# legatus_1_3.net
KiCad netlist of a schematic drawn in EAGLE
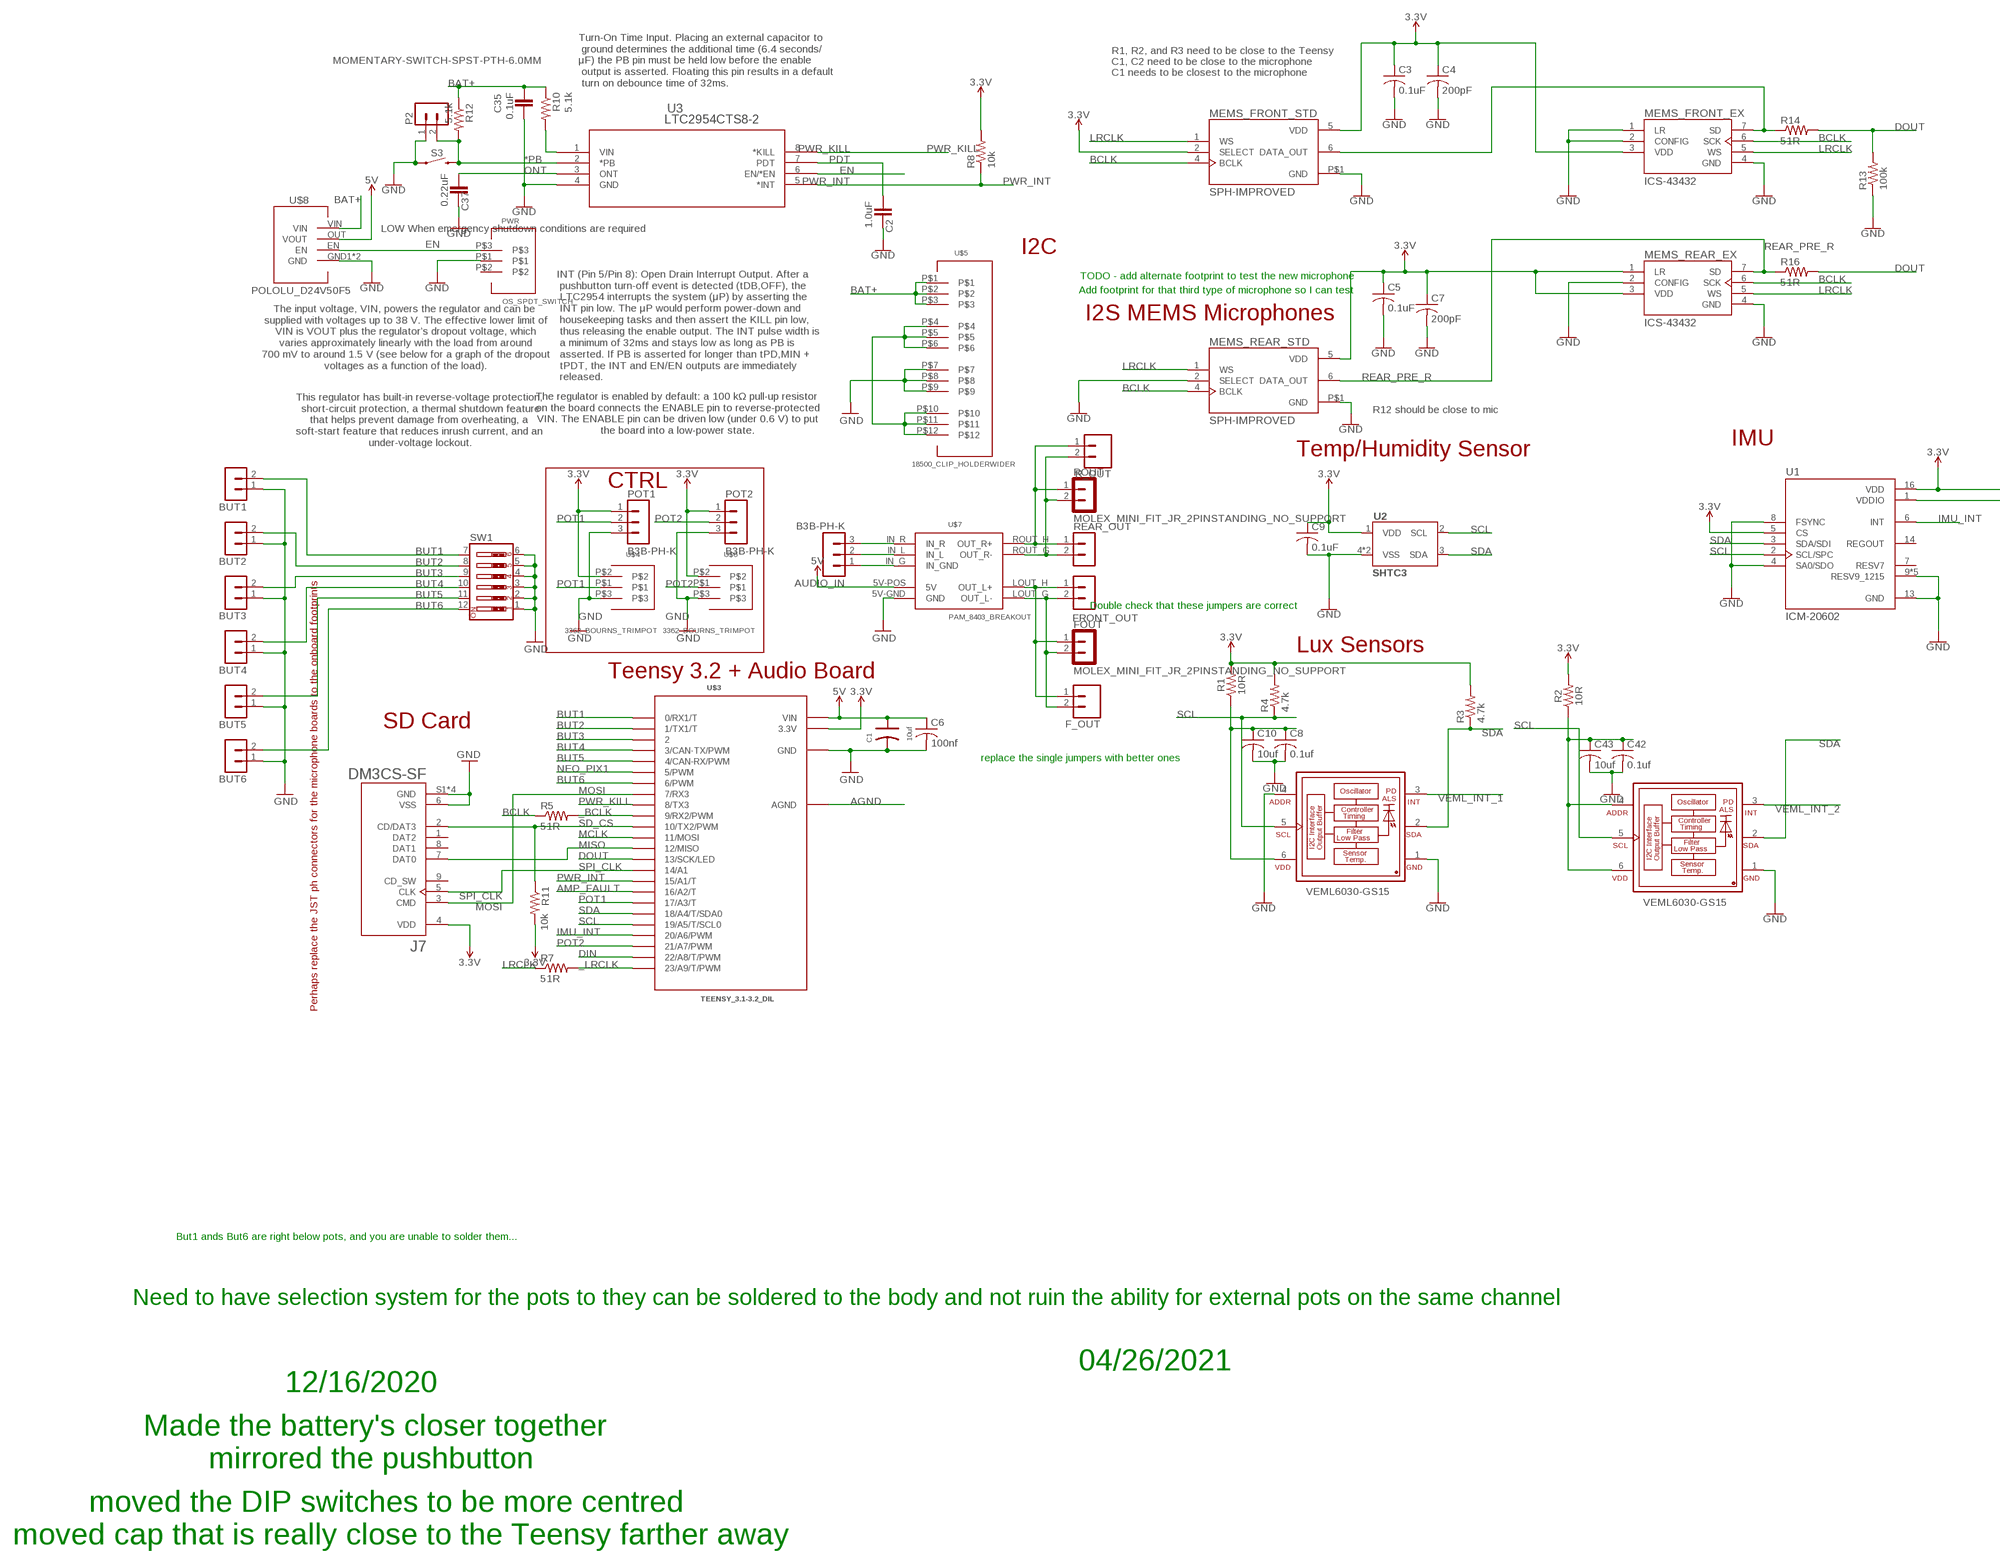
[diagram p0: schematic, sheet 1, part 1 of 2]
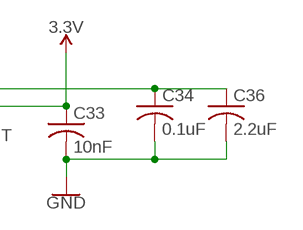
[diagram p1: schematic, sheet 1, part 2 of 2]
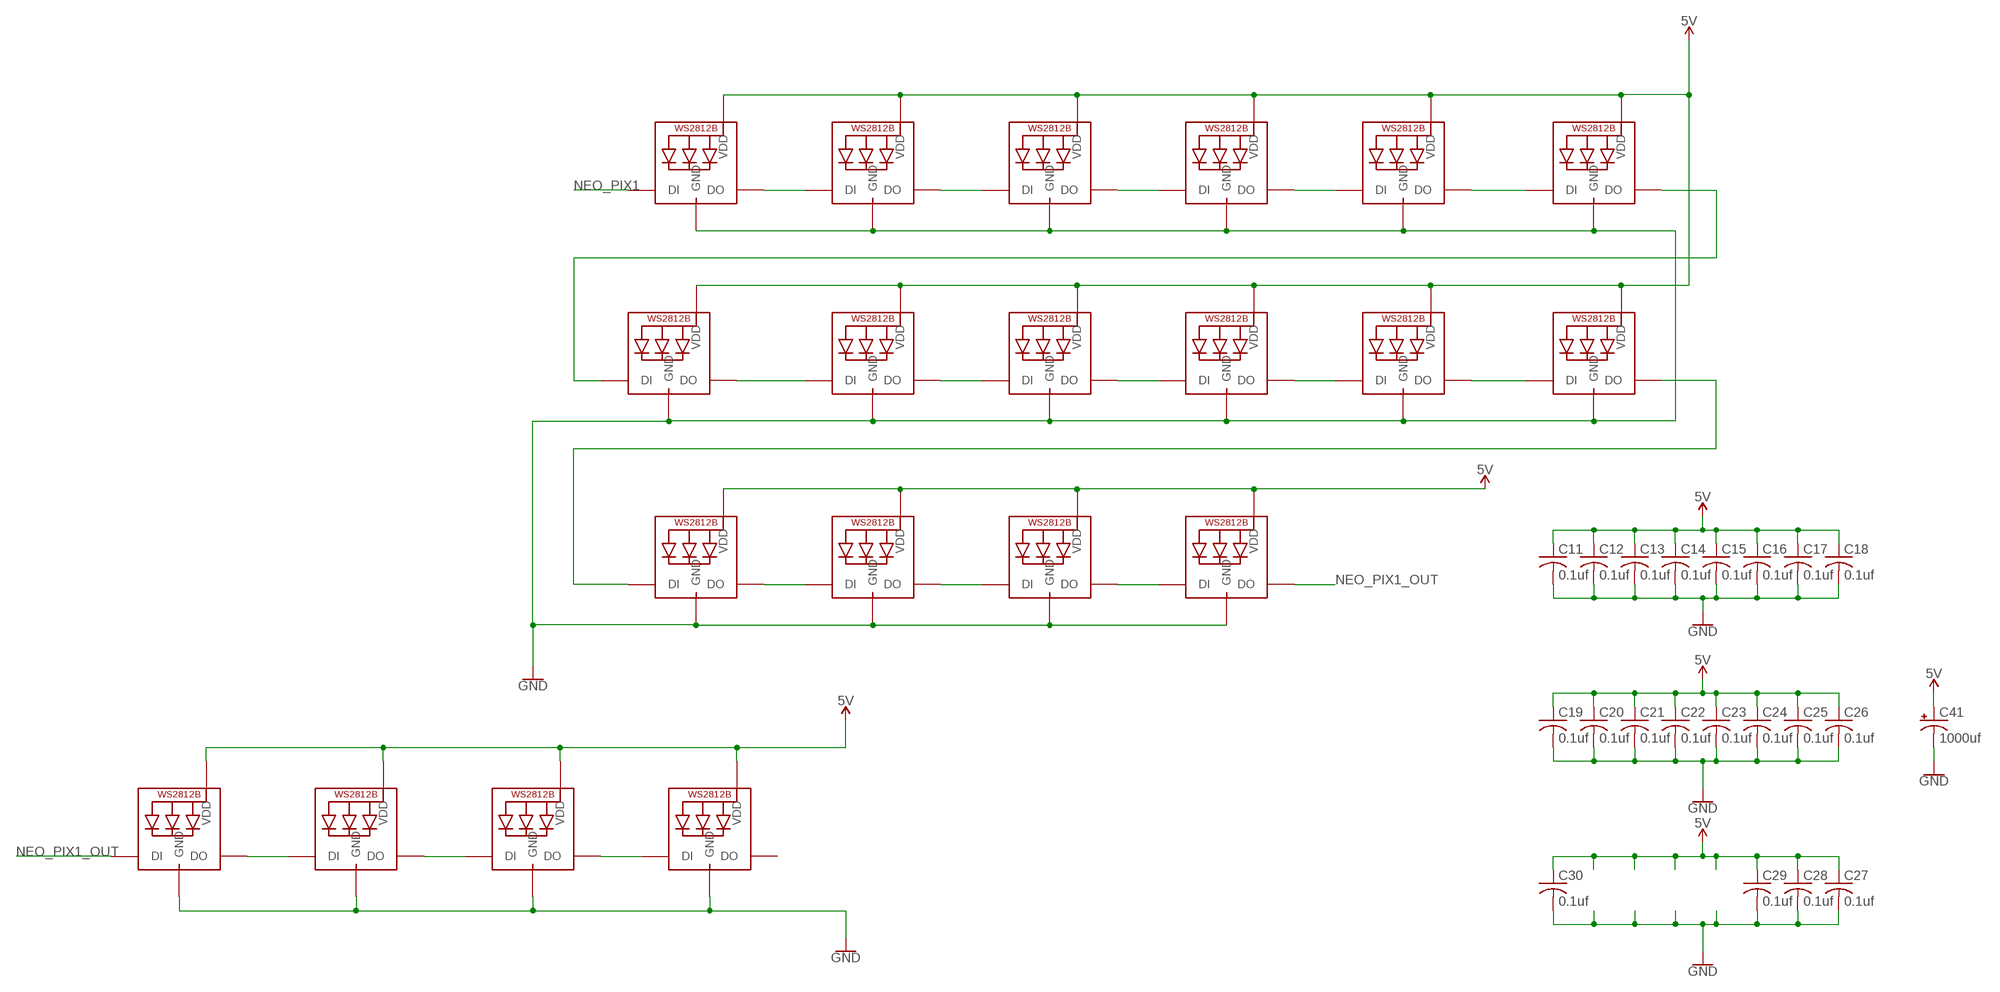
[diagram p2: schematic, sheet 2]

(export (version "E")
  (design (tool "Eeschema 10.0.6"))
  (components
    (comp (ref "C11")
      (value "0.1uf")
      (footprint "eagle-import:C0805")
      (libsource (lib "eagle-import") (part "rcl_334_C-USC0805"))
    )
    (comp (ref "C12")
      (value "0.1uf")
      (footprint "eagle-import:C0805")
      (libsource (lib "eagle-import") (part "rcl_334_C-USC0805"))
    )
    (comp (ref "C13")
      (value "0.1uf")
      (footprint "eagle-import:C0805")
      (libsource (lib "eagle-import") (part "rcl_334_C-USC0805"))
    )
    (comp (ref "C14")
      (value "0.1uf")
      (footprint "eagle-import:C0805")
      (libsource (lib "eagle-import") (part "rcl_334_C-USC0805"))
    )
    (comp (ref "C15")
      (value "0.1uf")
      (footprint "eagle-import:C0805")
      (libsource (lib "eagle-import") (part "rcl_334_C-USC0805"))
    )
    (comp (ref "C16")
      (value "0.1uf")
      (footprint "eagle-import:C0805")
      (libsource (lib "eagle-import") (part "rcl_334_C-USC0805"))
    )
    (comp (ref "C17")
      (value "0.1uf")
      (footprint "eagle-import:C0805")
      (libsource (lib "eagle-import") (part "rcl_334_C-USC0805"))
    )
    (comp (ref "C18")
      (value "0.1uf")
      (footprint "eagle-import:C0805")
      (libsource (lib "eagle-import") (part "rcl_334_C-USC0805"))
    )
    (comp (ref "C19")
      (value "0.1uf")
      (footprint "eagle-import:C0805")
      (libsource (lib "eagle-import") (part "rcl_334_C-USC0805"))
    )
    (comp (ref "C20")
      (value "0.1uf")
      (footprint "eagle-import:C0805")
      (libsource (lib "eagle-import") (part "rcl_334_C-USC0805"))
    )
    (comp (ref "C21")
      (value "0.1uf")
      (footprint "eagle-import:C0805")
      (libsource (lib "eagle-import") (part "rcl_334_C-USC0805"))
    )
    (comp (ref "C22")
      (value "0.1uf")
      (footprint "eagle-import:C0805")
      (libsource (lib "eagle-import") (part "rcl_334_C-USC0805"))
    )
    (comp (ref "C23")
      (value "0.1uf")
      (footprint "eagle-import:C0805")
      (libsource (lib "eagle-import") (part "rcl_334_C-USC0805"))
    )
    (comp (ref "C24")
      (value "0.1uf")
      (footprint "eagle-import:C0805")
      (libsource (lib "eagle-import") (part "rcl_334_C-USC0805"))
    )
    (comp (ref "C25")
      (value "0.1uf")
      (footprint "eagle-import:C0805")
      (libsource (lib "eagle-import") (part "rcl_334_C-USC0805"))
    )
    (comp (ref "C26")
      (value "0.1uf")
      (footprint "eagle-import:C0805")
      (libsource (lib "eagle-import") (part "rcl_334_C-USC0805"))
    )
    (comp (ref "C27")
      (value "0.1uf")
      (footprint "eagle-import:C0805")
      (libsource (lib "eagle-import") (part "rcl_334_C-USC0805"))
    )
    (comp (ref "C28")
      (value "0.1uf")
      (footprint "eagle-import:C0805")
      (libsource (lib "eagle-import") (part "rcl_334_C-USC0805"))
    )
    (comp (ref "C29")
      (value "0.1uf")
      (footprint "eagle-import:C0805")
      (libsource (lib "eagle-import") (part "rcl_334_C-USC0805"))
    )
    (comp (ref "C30")
      (value "0.1uf")
      (footprint "eagle-import:C0805")
      (libsource (lib "eagle-import") (part "rcl_334_C-USC0805"))
    )
    (comp (ref "C41")
      (value "1000uf")
      (footprint "eagle-import:153CLV-1010")
      (libsource (lib "eagle-import") (part "CPOL-US153CLV-1010"))
    )
    (comp (ref "LED1")
      (value "WS2812B_5050N")
      (footprint "eagle-import:WS2812B-NARROW")
      (libsource (lib "eagle-import") (part "WS2812B_5050N"))
    )
    (comp (ref "LED2")
      (value "WS2812B_5050N")
      (footprint "eagle-import:WS2812B-NARROW")
      (libsource (lib "eagle-import") (part "WS2812B_5050N"))
    )
    (comp (ref "LED3")
      (value "WS2812B_5050N")
      (footprint "eagle-import:WS2812B-NARROW")
      (libsource (lib "eagle-import") (part "WS2812B_5050N"))
    )
    (comp (ref "LED4")
      (value "WS2812B_5050N")
      (footprint "eagle-import:WS2812B-NARROW")
      (libsource (lib "eagle-import") (part "WS2812B_5050N"))
    )
    (comp (ref "LED5")
      (value "WS2812B_5050N")
      (footprint "eagle-import:WS2812B-NARROW")
      (libsource (lib "eagle-import") (part "WS2812B_5050N"))
    )
    (comp (ref "LED6")
      (value "WS2812B_5050N")
      (footprint "eagle-import:WS2812B-NARROW")
      (libsource (lib "eagle-import") (part "WS2812B_5050N"))
    )
    (comp (ref "LED7")
      (value "WS2812B_5050N")
      (footprint "eagle-import:WS2812B-NARROW")
      (libsource (lib "eagle-import") (part "WS2812B_5050N"))
    )
    (comp (ref "LED8")
      (value "WS2812B_5050N")
      (footprint "eagle-import:WS2812B-NARROW")
      (libsource (lib "eagle-import") (part "WS2812B_5050N"))
    )
    (comp (ref "LED9")
      (value "WS2812B_5050N")
      (footprint "eagle-import:WS2812B-NARROW")
      (libsource (lib "eagle-import") (part "WS2812B_5050N"))
    )
    (comp (ref "LED10")
      (value "WS2812B_5050N")
      (footprint "eagle-import:WS2812B-NARROW")
      (libsource (lib "eagle-import") (part "WS2812B_5050N"))
    )
    (comp (ref "LED11")
      (value "WS2812B_5050N")
      (footprint "eagle-import:WS2812B-NARROW")
      (libsource (lib "eagle-import") (part "WS2812B_5050N"))
    )
    (comp (ref "LED12")
      (value "WS2812B_5050N")
      (footprint "eagle-import:WS2812B-NARROW")
      (libsource (lib "eagle-import") (part "WS2812B_5050N"))
    )
    (comp (ref "LED13")
      (value "WS2812B_5050N")
      (footprint "eagle-import:WS2812B-NARROW")
      (libsource (lib "eagle-import") (part "WS2812B_5050N"))
    )
    (comp (ref "LED14")
      (value "WS2812B_5050N")
      (footprint "eagle-import:WS2812B-NARROW")
      (libsource (lib "eagle-import") (part "WS2812B_5050N"))
    )
    (comp (ref "LED15")
      (value "WS2812B_5050N")
      (footprint "eagle-import:WS2812B-NARROW")
      (libsource (lib "eagle-import") (part "WS2812B_5050N"))
    )
    (comp (ref "LED16")
      (value "WS2812B_5050N")
      (footprint "eagle-import:WS2812B-NARROW")
      (libsource (lib "eagle-import") (part "WS2812B_5050N"))
    )
    (comp (ref "LED17")
      (value "WS2812B_5050N")
      (footprint "eagle-import:WS2812B-NARROW")
      (libsource (lib "eagle-import") (part "WS2812B_5050N"))
    )
    (comp (ref "LED18")
      (value "WS2812B_5050N")
      (footprint "eagle-import:WS2812B-NARROW")
      (libsource (lib "eagle-import") (part "WS2812B_5050N"))
    )
    (comp (ref "LED19")
      (value "WS2812B_5050N")
      (footprint "eagle-import:WS2812B-NARROW")
      (libsource (lib "eagle-import") (part "WS2812B_5050N"))
    )
    (comp (ref "LED20")
      (value "WS2812B_5050N")
      (footprint "eagle-import:WS2812B-NARROW")
      (libsource (lib "eagle-import") (part "WS2812B_5050N"))
    )
    (comp (ref "AUDIO_IN")
      (value "B3B-PH-K")
      (footprint "eagle-import:B3B-PH-K")
      (libsource (lib "eagle-import") (part "B3B-PH-K"))
    )
    (comp (ref "BUT1")
      (value "B2B-PH-K")
      (footprint "eagle-import:B2B-PH-K")
      (libsource (lib "eagle-import") (part "B2B-PH-K"))
    )
    (comp (ref "BUT2")
      (value "B2B-PH-K")
      (footprint "eagle-import:B2B-PH-K")
      (libsource (lib "eagle-import") (part "B2B-PH-K"))
    )
    (comp (ref "BUT3")
      (value "B2B-PH-K")
      (footprint "eagle-import:B2B-PH-K")
      (libsource (lib "eagle-import") (part "B2B-PH-K"))
    )
    (comp (ref "BUT4")
      (value "B2B-PH-K")
      (footprint "eagle-import:B2B-PH-K")
      (libsource (lib "eagle-import") (part "B2B-PH-K"))
    )
    (comp (ref "BUT5")
      (value "B2B-PH-K")
      (footprint "eagle-import:B2B-PH-K")
      (libsource (lib "eagle-import") (part "B2B-PH-K"))
    )
    (comp (ref "BUT6")
      (value "B2B-PH-K")
      (footprint "eagle-import:B2B-PH-K")
      (libsource (lib "eagle-import") (part "B2B-PH-K"))
    )
    (comp (ref "C1")
      (value "10uf")
      (footprint "eagle-import:PC-D5.3MM")
      (fields (field (name "MPN") "KS 100uF/16V"))
      (libsource (lib "eagle-import") (part "DIP-ALUMINUM-47UF-16V(D5-H7MM)"))
    )
    (comp (ref "C2")
      (value "1.0uF")
      (footprint "eagle-import:CAPC2012X110")
      (libsource (lib "eagle-import") (part "CCHIP-0805(2012-METRIC)_"))
    )
    (comp (ref "C3")
      (value "0.1uF")
      (footprint "eagle-import:C0805")
      (libsource (lib "eagle-import") (part "rcl_334_C-USC0805"))
    )
    (comp (ref "C4")
      (value "200pF")
      (footprint "eagle-import:C0805")
      (libsource (lib "eagle-import") (part "rcl_334_C-USC0805"))
    )
    (comp (ref "C5")
      (value "0.1uF")
      (footprint "eagle-import:C0805")
      (libsource (lib "eagle-import") (part "rcl_334_C-USC0805"))
    )
    (comp (ref "C6")
      (value "100nf")
      (footprint "eagle-import:C2012")
      (libsource (lib "eagle-import") (part "C-USC2012"))
    )
    (comp (ref "C7")
      (value "200pF")
      (footprint "eagle-import:C0805")
      (libsource (lib "eagle-import") (part "rcl_334_C-USC0805"))
    )
    (comp (ref "C8")
      (value "0.1uf")
      (footprint "eagle-import:C0805")
      (libsource (lib "eagle-import") (part "rcl_334_C-USC0805"))
    )
    (comp (ref "C9")
      (value "0.1uF")
      (footprint "eagle-import:C0805")
      (libsource (lib "eagle-import") (part "rcl_334_C-USC0805"))
    )
    (comp (ref "C10")
      (value "10uf")
      (footprint "eagle-import:C0805")
      (libsource (lib "eagle-import") (part "rcl_334_C-USC0805"))
    )
    (comp (ref "C33")
      (value "10nF")
      (footprint "eagle-import:C0805")
      (libsource (lib "eagle-import") (part "rcl_334_C-USC0805"))
    )
    (comp (ref "C34")
      (value "0.1uF")
      (footprint "eagle-import:C0805")
      (libsource (lib "eagle-import") (part "rcl_334_C-USC0805"))
    )
    (comp (ref "C35")
      (value "0.1uF")
      (footprint "eagle-import:CAPC2012X110")
      (libsource (lib "eagle-import") (part "CCHIP-0805(2012-METRIC)_"))
    )
    (comp (ref "C36")
      (value "2.2uF")
      (footprint "eagle-import:C0805")
      (libsource (lib "eagle-import") (part "rcl_334_C-USC0805"))
    )
    (comp (ref "C37")
      (value "0.22uF")
      (footprint "eagle-import:CAPC2012X110")
      (libsource (lib "eagle-import") (part "CCHIP-0805(2012-METRIC)_"))
    )
    (comp (ref "C42")
      (value "0.1uf")
      (footprint "eagle-import:C0805")
      (libsource (lib "eagle-import") (part "rcl_334_C-USC0805"))
    )
    (comp (ref "C43")
      (value "10uf")
      (footprint "eagle-import:C0805")
      (libsource (lib "eagle-import") (part "rcl_334_C-USC0805"))
    )
    (comp (ref "FOUT")
      (value "MOLEX_MINI_FIT_JR_2PINSTANDING_NO_SUPPORT")
      (footprint "eagle-import:MOLEX_MINI_FIT_JR_2_PIN_STANDING_NO_SUPPORTS")
      (libsource (lib "eagle-import") (part "MOLEX_MINI_FIT_JR_2PINSTANDING_NO_SUPPORT"))
    )
    (comp (ref "FRONT_OUT")
      (value "B2B-PH-K")
      (footprint "eagle-import:B2B-PH-K")
      (libsource (lib "eagle-import") (part "B2B-PH-K"))
    )
    (comp (ref "F_OUT")
      (value "CONN_02")
      (footprint "eagle-import:1X02")
      (libsource (lib "eagle-import") (part "CONN_02"))
    )
    (comp (ref "J7")
      (value "DM3CS-SF")
      (footprint "eagle-import:HRS_DM3CS-SF")
      (fields (field (name "MF") "Hirose"))
      (libsource (lib "eagle-import") (part "DM3CS-SF"))
    )
    (comp (ref "MEMS_FRONT_EX")
      (value "ICS-43432")
      (footprint "eagle-import:ICS-43432")
      (fields
        (field (name "DIGIKEY_PARTNO") "1428-1053-2-ND")
        (field (name "MANUFACTURER") "TDK InvenSense")
        (field (name "CREATED_BY") "PCBLayout.com")
      )
      (libsource (lib "eagle-import") (part "ICS-43432"))
    )
    (comp (ref "MEMS_FRONT_STD")
      (value "SPH-IMPROVED")
      (footprint "eagle-import:MIC_SPH0645LM4H-B_LARGER_RING")
      (libsource (lib "eagle-import") (part "SPH-IMPROVED"))
    )
    (comp (ref "MEMS_REAR_EX")
      (value "ICS-43432")
      (footprint "eagle-import:ICS-43432")
      (fields
        (field (name "DIGIKEY_PARTNO") "1428-1053-2-ND")
        (field (name "MANUFACTURER") "TDK InvenSense")
        (field (name "CREATED_BY") "PCBLayout.com")
      )
      (libsource (lib "eagle-import") (part "ICS-43432"))
    )
    (comp (ref "MEMS_REAR_STD")
      (value "SPH-IMPROVED")
      (footprint "eagle-import:MIC_SPH0645LM4H-B_LARGER_RING")
      (libsource (lib "eagle-import") (part "SPH-IMPROVED"))
    )
    (comp (ref "P2")
      (value "B2B-PH-K")
      (footprint "eagle-import:B2B-PH-K")
      (libsource (lib "eagle-import") (part "B2B-PH-K"))
    )
    (comp (ref "POT1")
      (value "B3B-PH-K")
      (footprint "eagle-import:B3B-PH-K")
      (libsource (lib "eagle-import") (part "B3B-PH-K"))
    )
    (comp (ref "POT2")
      (value "B3B-PH-K")
      (footprint "eagle-import:B3B-PH-K")
      (libsource (lib "eagle-import") (part "B3B-PH-K"))
    )
    (comp (ref "PWR")
      (value "OS_SPDT_SWITCH")
      (footprint "eagle-import:OS_SPDT_SLIDE_SWITCH")
      (libsource (lib "eagle-import") (part "OS_SPDT_SWITCH"))
    )
    (comp (ref "R1")
      (value "10R")
      (footprint "eagle-import:R0805")
      (libsource (lib "eagle-import") (part "audio amplifier example_970892_R-US_R0805"))
    )
    (comp (ref "R2")
      (value "10R")
      (footprint "eagle-import:R0805")
      (libsource (lib "eagle-import") (part "audio amplifier example_970892_R-US_R0805"))
    )
    (comp (ref "R3")
      (value "4.7k")
      (footprint "eagle-import:M0805")
      (libsource (lib "eagle-import") (part "adafruit_420_R-US_M0805"))
    )
    (comp (ref "R4")
      (value "4.7k")
      (footprint "eagle-import:M0805")
      (libsource (lib "eagle-import") (part "adafruit_420_R-US_M0805"))
    )
    (comp (ref "R5")
      (value "51R")
      (footprint "eagle-import:M0805")
      (libsource (lib "eagle-import") (part "adafruit_420_R-US_M0805"))
    )
    (comp (ref "R7")
      (value "51R")
      (footprint "eagle-import:M0805")
      (libsource (lib "eagle-import") (part "adafruit_420_R-US_M0805"))
    )
    (comp (ref "R8")
      (value "10k")
      (footprint "eagle-import:R0805")
      (libsource (lib "eagle-import") (part "R-US_R0805"))
    )
    (comp (ref "R10")
      (value "5.1k")
      (footprint "eagle-import:R0805")
      (libsource (lib "eagle-import") (part "R-US_R0805"))
    )
    (comp (ref "R11")
      (value "10k")
      (footprint "eagle-import:M0805")
      (libsource (lib "eagle-import") (part "rcl_R-US_M0805"))
    )
    (comp (ref "R12")
      (value "5.1k")
      (footprint "eagle-import:R0805")
      (libsource (lib "eagle-import") (part "R-US_R0805"))
    )
    (comp (ref "R13")
      (value "100k")
      (footprint "eagle-import:M0805")
      (libsource (lib "eagle-import") (part "adafruit_420_R-US_M0805"))
    )
    (comp (ref "R14")
      (value "51R")
      (footprint "eagle-import:M0805")
      (libsource (lib "eagle-import") (part "adafruit_420_R-US_M0805"))
    )
    (comp (ref "R16")
      (value "51R")
      (footprint "eagle-import:M0805")
      (libsource (lib "eagle-import") (part "adafruit_420_R-US_M0805"))
    )
    (comp (ref "REAR_OUT")
      (value "B2B-PH-K")
      (footprint "eagle-import:B2B-PH-K")
      (libsource (lib "eagle-import") (part "B2B-PH-K"))
    )
    (comp (ref "ROUT")
      (value "MOLEX_MINI_FIT_JR_2PINSTANDING_NO_SUPPORT")
      (footprint "eagle-import:MOLEX_MINI_FIT_JR_2_PIN_STANDING_NO_SUPPORTS")
      (libsource (lib "eagle-import") (part "MOLEX_MINI_FIT_JR_2PINSTANDING_NO_SUPPORT"))
    )
    (comp (ref "R_OUT")
      (value "CONN_02")
      (footprint "eagle-import:1X02")
      (libsource (lib "eagle-import") (part "CONN_02"))
    )
    (comp (ref "S3")
      (value "MOMENTARY-SWITCH-SPST-PTH-6.0MM")
      (footprint "eagle-import:TACTILE_SWITCH_PTH_6.0MM")
      (libsource (lib "eagle-import") (part "MOMENTARY-SWITCH-SPST-PTH-6.0MM"))
    )
    (comp (ref "SW1")
      (value "SW_DIP-6")
      (footprint "eagle-import:EDG-06")
      (libsource (lib "eagle-import") (part "SW_DIP-6"))
    )
    (comp (ref "U$3")
      (value "TEENSY_3.1-3.2_DIL")
      (footprint "eagle-import:TEENSY_3.0-3.2&LC_DIL")
      (libsource (lib "eagle-import") (part "TEENSY_3.1-3.2_DIL"))
    )
    (comp (ref "U$4")
      (value "3362_BOURNS_TRIMPOT")
      (footprint "eagle-import:3362_BOURNS_TRIMPOT")
      (libsource (lib "eagle-import") (part "3362_BOURNS_TRIMPOT"))
    )
    (comp (ref "U$5")
      (value "18500_CLIP_HOLDERWIDER")
      (footprint "eagle-import:3PINBATTERY_CLIP_WIDER")
      (libsource (lib "eagle-import") (part "18500_CLIP_HOLDERWIDER"))
    )
    (comp (ref "U$6")
      (value "3362_BOURNS_TRIMPOT")
      (footprint "eagle-import:3362_BOURNS_TRIMPOT")
      (libsource (lib "eagle-import") (part "3362_BOURNS_TRIMPOT"))
    )
    (comp (ref "U$7")
      (value "PAM_8403_BREAKOUT")
      (footprint "eagle-import:PAM8403_BREAKOUT")
      (libsource (lib "eagle-import") (part "PAM_8403_BREAKOUT"))
    )
    (comp (ref "U$8")
      (value "POLOLU_D24V50F5")
      (footprint "eagle-import:POLOLU_D24V50F5")
      (libsource (lib "eagle-import") (part "POLOLU_D24V50F5"))
    )
    (comp (ref "U1")
      (value "ICM-20602")
      (footprint "eagle-import:PQFN50P300X300X80-16N")
      (fields (field (name "MF") "TDK InvenSense"))
      (libsource (lib "eagle-import") (part "ICM-20602"))
    )
    (comp (ref "U2")
      (value "SHTC3")
      (footprint "eagle-import:SHTC3")
      (libsource (lib "eagle-import") (part "SHTC3"))
    )
    (comp (ref "U3")
      (value "LTC2954CTS8-2")
      (footprint "eagle-import:TSOT-23_TS8")
      (fields (field (name "MF") "Analog Devices / Linear Technology"))
      (libsource (lib "eagle-import") (part "LTC2954CTS8-2"))
    )
    (comp (ref "VMEL_FRONT")
      (value "VEML6030-GS15")
      (footprint "eagle-import:VISHAY_VEML6030_2X2X0.87")
      (fields (field (name "MF") "Vishay Semiconductor"))
      (libsource (lib "eagle-import") (part "VEML6030-GS15"))
    )
    (comp (ref "VMEL_REAR")
      (value "VEML6030-GS15")
      (footprint "eagle-import:VISHAY_VEML6030_2X2X0.87")
      (fields (field (name "MF") "Vishay Semiconductor"))
      (libsource (lib "eagle-import") (part "VEML6030-GS15"))
    )
  )
  (nets
    (net (code "1") (name "*PB") (class "Default")
      (node (ref "P2") (pin "2") (pinfunction "2_2") (pintype "passive"))
      (node (ref "R12") (pin "2") (pinfunction "2_2") (pintype "passive"))
      (node (ref "S3") (pin "3") (pinfunction "2_3") (pintype "passive"))
      (node (ref "U3") (pin "2") (pinfunction "*PB_2") (pintype "input"))
    )
    (net (code "2") (name "3.3V") (class "Default")
      (node (ref "C3") (pin "1") (pinfunction "1_1") (pintype "passive"))
      (node (ref "C33") (pin "1") (pinfunction "1_1") (pintype "passive"))
      (node (ref "C34") (pin "1") (pinfunction "1_1") (pintype "passive"))
      (node (ref "C36") (pin "1") (pinfunction "1_1") (pintype "passive"))
      (node (ref "C4") (pin "1") (pinfunction "1_1") (pintype "passive"))
      (node (ref "C5") (pin "1") (pinfunction "1_1") (pintype "passive"))
      (node (ref "C7") (pin "1") (pinfunction "1_1") (pintype "passive"))
      (node (ref "C9") (pin "1") (pinfunction "1_1") (pintype "passive"))
      (node (ref "J7") (pin "4") (pinfunction "VDD_4") (pintype "passive"))
      (node (ref "MEMS_FRONT_EX") (pin "3") (pinfunction "VDD_3") (pintype "power_in"))
      (node (ref "MEMS_FRONT_STD") (pin "2") (pinfunction "SELECT_2") (pintype "input"))
      (node (ref "MEMS_FRONT_STD") (pin "5") (pinfunction "VDD_5") (pintype "power_in"))
      (node (ref "MEMS_REAR_EX") (pin "1") (pinfunction "LR_1") (pintype "input"))
      (node (ref "MEMS_REAR_EX") (pin "3") (pinfunction "VDD_3") (pintype "power_in"))
      (node (ref "MEMS_REAR_STD") (pin "5") (pinfunction "VDD_5") (pintype "power_in"))
      (node (ref "POT1") (pin "1") (pinfunction "1_1") (pintype "passive"))
      (node (ref "POT2") (pin "1") (pinfunction "1_1") (pintype "passive"))
      (node (ref "R1") (pin "2") (pinfunction "2_2") (pintype "passive"))
      (node (ref "R11") (pin "2") (pinfunction "2_2") (pintype "passive"))
      (node (ref "R2") (pin "2") (pinfunction "2_2") (pintype "passive"))
      (node (ref "R3") (pin "2") (pinfunction "2_2") (pintype "passive"))
      (node (ref "R4") (pin "2") (pinfunction "2_2") (pintype "passive"))
      (node (ref "R8") (pin "2") (pinfunction "2_2") (pintype "passive"))
      (node (ref "U$3") (pin "3.3V") (pinfunction "3.3V_3.3V") (pintype "power_in"))
      (node (ref "U$4") (pin "P$2") (pinfunction "P$2_P$2") (pintype "bidirectional"))
      (node (ref "U$6") (pin "P$2") (pinfunction "P$2_P$2") (pintype "bidirectional"))
      (node (ref "U1") (pin "1") (pinfunction "VDDIO_1") (pintype "power_in"))
      (node (ref "U1") (pin "16") (pinfunction "VDD_16") (pintype "power_in"))
      (node (ref "U1") (pin "5") (pinfunction "CS_5") (pintype "input"))
      (node (ref "U2") (pin "1") (pinfunction "VDD_1") (pintype "bidirectional"))
    )
    (net (code "3") (name "5V") (class "Default")
      (node (ref "C1") (pin "+") (pinfunction "+_+") (pintype "passive"))
      (node (ref "C11") (pin "1") (pinfunction "1_1") (pintype "passive"))
      (node (ref "C12") (pin "1") (pinfunction "1_1") (pintype "passive"))
      (node (ref "C13") (pin "1") (pinfunction "1_1") (pintype "passive"))
      (node (ref "C14") (pin "1") (pinfunction "1_1") (pintype "passive"))
      (node (ref "C15") (pin "1") (pinfunction "1_1") (pintype "passive"))
      (node (ref "C16") (pin "1") (pinfunction "1_1") (pintype "passive"))
      (node (ref "C17") (pin "1") (pinfunction "1_1") (pintype "passive"))
      (node (ref "C18") (pin "1") (pinfunction "1_1") (pintype "passive"))
      (node (ref "C19") (pin "1") (pinfunction "1_1") (pintype "passive"))
      (node (ref "C20") (pin "1") (pinfunction "1_1") (pintype "passive"))
      (node (ref "C21") (pin "1") (pinfunction "1_1") (pintype "passive"))
      (node (ref "C22") (pin "1") (pinfunction "1_1") (pintype "passive"))
      (node (ref "C23") (pin "1") (pinfunction "1_1") (pintype "passive"))
      (node (ref "C24") (pin "1") (pinfunction "1_1") (pintype "passive"))
      (node (ref "C25") (pin "1") (pinfunction "1_1") (pintype "passive"))
      (node (ref "C26") (pin "1") (pinfunction "1_1") (pintype "passive"))
      (node (ref "C27") (pin "1") (pinfunction "1_1") (pintype "passive"))
      (node (ref "C28") (pin "1") (pinfunction "1_1") (pintype "passive"))
      (node (ref "C29") (pin "1") (pinfunction "1_1") (pintype "passive"))
      (node (ref "C30") (pin "1") (pinfunction "1_1") (pintype "passive"))
      (node (ref "C41") (pin "+") (pinfunction "+_+") (pintype "passive"))
      (node (ref "C6") (pin "1") (pinfunction "1_1") (pintype "passive"))
      (node (ref "LED1") (pin "1-VDD") (pinfunction "VDD_1-VDD") (pintype "power_in"))
      (node (ref "LED10") (pin "1-VDD") (pinfunction "VDD_1-VDD") (pintype "power_in"))
      (node (ref "LED11") (pin "1-VDD") (pinfunction "VDD_1-VDD") (pintype "power_in"))
      (node (ref "LED12") (pin "1-VDD") (pinfunction "VDD_1-VDD") (pintype "power_in"))
      (node (ref "LED13") (pin "1-VDD") (pinfunction "VDD_1-VDD") (pintype "power_in"))
      (node (ref "LED14") (pin "1-VDD") (pinfunction "VDD_1-VDD") (pintype "power_in"))
      (node (ref "LED15") (pin "1-VDD") (pinfunction "VDD_1-VDD") (pintype "power_in"))
      (node (ref "LED16") (pin "1-VDD") (pinfunction "VDD_1-VDD") (pintype "power_in"))
      (node (ref "LED17") (pin "1-VDD") (pinfunction "VDD_1-VDD") (pintype "power_in"))
      (node (ref "LED18") (pin "1-VDD") (pinfunction "VDD_1-VDD") (pintype "power_in"))
      (node (ref "LED19") (pin "1-VDD") (pinfunction "VDD_1-VDD") (pintype "power_in"))
      (node (ref "LED2") (pin "1-VDD") (pinfunction "VDD_1-VDD") (pintype "power_in"))
      (node (ref "LED20") (pin "1-VDD") (pinfunction "VDD_1-VDD") (pintype "power_in"))
      (node (ref "LED3") (pin "1-VDD") (pinfunction "VDD_1-VDD") (pintype "power_in"))
      (node (ref "LED4") (pin "1-VDD") (pinfunction "VDD_1-VDD") (pintype "power_in"))
      (node (ref "LED5") (pin "1-VDD") (pinfunction "VDD_1-VDD") (pintype "power_in"))
      (node (ref "LED6") (pin "1-VDD") (pinfunction "VDD_1-VDD") (pintype "power_in"))
      (node (ref "LED7") (pin "1-VDD") (pinfunction "VDD_1-VDD") (pintype "power_in"))
      (node (ref "LED8") (pin "1-VDD") (pinfunction "VDD_1-VDD") (pintype "power_in"))
      (node (ref "LED9") (pin "1-VDD") (pinfunction "VDD_1-VDD") (pintype "power_in"))
      (node (ref "U$3") (pin "VIN") (pinfunction "VIN_VIN") (pintype "power_in"))
      (node (ref "U$7") (pin "5V-POS") (pinfunction "5V_5V-POS") (pintype "bidirectional"))
      (node (ref "U$8") (pin "OUT") (pinfunction "VOUT_OUT") (pintype "bidirectional"))
    )
    (net (code "4") (name "AGND") (class "Default")
      (node (ref "U$3") (pin "AGND") (pinfunction "AGND_AGND") (pintype "power_in"))
    )
    (net (code "5") (name "AMP_FAULT") (class "Default")
      (node (ref "U$3") (pin "16/A2") (pinfunction "16/A2/T_16/A2") (pintype "bidirectional"))
    )
    (net (code "6") (name "BAT+") (class "Default")
      (node (ref "C35") (pin "1") (pinfunction "1_1") (pintype "passive"))
      (node (ref "R10") (pin "1") (pinfunction "1_1") (pintype "passive"))
      (node (ref "R12") (pin "1") (pinfunction "1_1") (pintype "passive"))
      (node (ref "U$5") (pin "P$1") (pinfunction "P$1_P$1") (pintype "bidirectional"))
      (node (ref "U$5") (pin "P$2") (pinfunction "P$2_P$2") (pintype "bidirectional"))
      (node (ref "U$5") (pin "P$3") (pinfunction "P$3_P$3") (pintype "bidirectional"))
      (node (ref "U$8") (pin "VIN") (pinfunction "VIN_VIN") (pintype "bidirectional"))
    )
    (net (code "7") (name "BCLK") (class "Default")
      (node (ref "MEMS_FRONT_EX") (pin "6") (pinfunction "SCK_6") (pintype "input"))
      (node (ref "MEMS_FRONT_STD") (pin "4") (pinfunction "BCLK_4") (pintype "input"))
      (node (ref "MEMS_REAR_EX") (pin "6") (pinfunction "SCK_6") (pintype "input"))
      (node (ref "MEMS_REAR_STD") (pin "4") (pinfunction "BCLK_4") (pintype "input"))
      (node (ref "R5") (pin "1") (pinfunction "1_1") (pintype "passive"))
    )
    (net (code "8") (name "BUT1") (class "Default")
      (node (ref "BUT1") (pin "2") (pinfunction "2_2") (pintype "passive"))
      (node (ref "SW1") (pin "7") (pinfunction "7_7") (pintype "passive"))
      (node (ref "U$3") (pin "0") (pinfunction "0/RX1/T_0") (pintype "bidirectional"))
    )
    (net (code "9") (name "BUT2") (class "Default")
      (node (ref "BUT2") (pin "2") (pinfunction "2_2") (pintype "passive"))
      (node (ref "SW1") (pin "8") (pinfunction "8_8") (pintype "passive"))
      (node (ref "U$3") (pin "1") (pinfunction "1/TX1/T_1") (pintype "bidirectional"))
    )
    (net (code "10") (name "BUT3") (class "Default")
      (node (ref "BUT3") (pin "2") (pinfunction "2_2") (pintype "passive"))
      (node (ref "SW1") (pin "9") (pinfunction "9_9") (pintype "passive"))
      (node (ref "U$3") (pin "2") (pinfunction "2_2") (pintype "bidirectional"))
    )
    (net (code "11") (name "BUT4") (class "Default")
      (node (ref "BUT4") (pin "2") (pinfunction "2_2") (pintype "passive"))
      (node (ref "SW1") (pin "10") (pinfunction "10_10") (pintype "passive"))
      (node (ref "U$3") (pin "3") (pinfunction "3/CAN-TX/PWM_3") (pintype "bidirectional"))
    )
    (net (code "12") (name "BUT5") (class "Default")
      (node (ref "BUT5") (pin "2") (pinfunction "2_2") (pintype "passive"))
      (node (ref "SW1") (pin "11") (pinfunction "11_11") (pintype "passive"))
      (node (ref "U$3") (pin "4") (pinfunction "4/CAN-RX/PWM_4") (pintype "bidirectional"))
    )
    (net (code "13") (name "BUT6") (class "Default")
      (node (ref "BUT6") (pin "2") (pinfunction "2_2") (pintype "passive"))
      (node (ref "SW1") (pin "12") (pinfunction "12_12") (pintype "passive"))
      (node (ref "U$3") (pin "6") (pinfunction "6/PWM_6") (pintype "bidirectional"))
    )
    (net (code "14") (name "DIN") (class "Default")
      (node (ref "U$3") (pin "22/A8") (pinfunction "22/A8/T/PWM_22/A8") (pintype "bidirectional"))
    )
    (net (code "15") (name "DOUT") (class "Default")
      (node (ref "R13") (pin "2") (pinfunction "2_2") (pintype "passive"))
      (node (ref "R14") (pin "2") (pinfunction "2_2") (pintype "passive"))
      (node (ref "R16") (pin "2") (pinfunction "2_2") (pintype "passive"))
      (node (ref "U$3") (pin "13") (pinfunction "13/SCK/LED_13") (pintype "bidirectional"))
    )
    (net (code "16") (name "EN") (class "Default")
      (node (ref "PWR") (pin "P$3") (pinfunction "P$3_P$3") (pintype "bidirectional"))
      (node (ref "U$8") (pin "EN") (pinfunction "EN_EN") (pintype "bidirectional"))
      (node (ref "U3") (pin "6") (pinfunction "EN/*EN_6") (pintype "output"))
    )
    (net (code "17") (name "GND") (class "Default")
      (node (ref "BUT1") (pin "1") (pinfunction "1_1") (pintype "passive"))
      (node (ref "BUT2") (pin "1") (pinfunction "1_1") (pintype "passive"))
      (node (ref "BUT3") (pin "1") (pinfunction "1_1") (pintype "passive"))
      (node (ref "BUT4") (pin "1") (pinfunction "1_1") (pintype "passive"))
      (node (ref "BUT5") (pin "1") (pinfunction "1_1") (pintype "passive"))
      (node (ref "BUT6") (pin "1") (pinfunction "1_1") (pintype "passive"))
      (node (ref "C1") (pin "-") (pinfunction "-_-") (pintype "passive"))
      (node (ref "C10") (pin "2") (pinfunction "2_2") (pintype "passive"))
      (node (ref "C11") (pin "2") (pinfunction "2_2") (pintype "passive"))
      (node (ref "C12") (pin "2") (pinfunction "2_2") (pintype "passive"))
      (node (ref "C13") (pin "2") (pinfunction "2_2") (pintype "passive"))
      (node (ref "C14") (pin "2") (pinfunction "2_2") (pintype "passive"))
      (node (ref "C15") (pin "2") (pinfunction "2_2") (pintype "passive"))
      (node (ref "C16") (pin "2") (pinfunction "2_2") (pintype "passive"))
      (node (ref "C17") (pin "2") (pinfunction "2_2") (pintype "passive"))
      (node (ref "C18") (pin "2") (pinfunction "2_2") (pintype "passive"))
      (node (ref "C19") (pin "2") (pinfunction "2_2") (pintype "passive"))
      (node (ref "C2") (pin "2") (pinfunction "2_2") (pintype "passive"))
      (node (ref "C20") (pin "2") (pinfunction "2_2") (pintype "passive"))
      (node (ref "C21") (pin "2") (pinfunction "2_2") (pintype "passive"))
      (node (ref "C22") (pin "2") (pinfunction "2_2") (pintype "passive"))
      (node (ref "C23") (pin "2") (pinfunction "2_2") (pintype "passive"))
      (node (ref "C24") (pin "2") (pinfunction "2_2") (pintype "passive"))
      (node (ref "C25") (pin "2") (pinfunction "2_2") (pintype "passive"))
      (node (ref "C26") (pin "2") (pinfunction "2_2") (pintype "passive"))
      (node (ref "C27") (pin "2") (pinfunction "2_2") (pintype "passive"))
      (node (ref "C28") (pin "2") (pinfunction "2_2") (pintype "passive"))
      (node (ref "C29") (pin "2") (pinfunction "2_2") (pintype "passive"))
      (node (ref "C3") (pin "2") (pinfunction "2_2") (pintype "passive"))
      (node (ref "C30") (pin "2") (pinfunction "2_2") (pintype "passive"))
      (node (ref "C33") (pin "2") (pinfunction "2_2") (pintype "passive"))
      (node (ref "C34") (pin "2") (pinfunction "2_2") (pintype "passive"))
      (node (ref "C35") (pin "2") (pinfunction "2_2") (pintype "passive"))
      (node (ref "C36") (pin "2") (pinfunction "2_2") (pintype "passive"))
      (node (ref "C37") (pin "2") (pinfunction "2_2") (pintype "passive"))
      (node (ref "C4") (pin "2") (pinfunction "2_2") (pintype "passive"))
      (node (ref "C41") (pin "-") (pinfunction "-_-") (pintype "passive"))
      (node (ref "C42") (pin "2") (pinfunction "2_2") (pintype "passive"))
      (node (ref "C43") (pin "2") (pinfunction "2_2") (pintype "passive"))
      (node (ref "C5") (pin "2") (pinfunction "2_2") (pintype "passive"))
      (node (ref "C6") (pin "2") (pinfunction "2_2") (pintype "passive"))
      (node (ref "C7") (pin "2") (pinfunction "2_2") (pintype "passive"))
      (node (ref "C8") (pin "2") (pinfunction "2_2") (pintype "passive"))
      (node (ref "C9") (pin "2") (pinfunction "2_2") (pintype "passive"))
      (node (ref "J7") (pin "6") (pinfunction "VSS_6") (pintype "passive"))
      (node (ref "J7") (pin "S1") (pinfunction "GND_S1") (pintype "passive"))
      (node (ref "J7") (pin "S2") (pinfunction "GND_S2") (pintype "passive"))
      (node (ref "J7") (pin "S3") (pinfunction "GND_S3") (pintype "passive"))
      (node (ref "J7") (pin "S5") (pinfunction "GND_S5") (pintype "passive"))
      (node (ref "LED1") (pin "3-GND") (pinfunction "GND_3-GND") (pintype "power_in"))
      (node (ref "LED10") (pin "3-GND") (pinfunction "GND_3-GND") (pintype "power_in"))
      (node (ref "LED11") (pin "3-GND") (pinfunction "GND_3-GND") (pintype "power_in"))
      (node (ref "LED12") (pin "3-GND") (pinfunction "GND_3-GND") (pintype "power_in"))
      (node (ref "LED13") (pin "3-GND") (pinfunction "GND_3-GND") (pintype "power_in"))
      (node (ref "LED14") (pin "3-GND") (pinfunction "GND_3-GND") (pintype "power_in"))
      (node (ref "LED15") (pin "3-GND") (pinfunction "GND_3-GND") (pintype "power_in"))
      (node (ref "LED16") (pin "3-GND") (pinfunction "GND_3-GND") (pintype "power_in"))
      (node (ref "LED17") (pin "3-GND") (pinfunction "GND_3-GND") (pintype "power_in"))
      (node (ref "LED18") (pin "3-GND") (pinfunction "GND_3-GND") (pintype "power_in"))
      (node (ref "LED19") (pin "3-GND") (pinfunction "GND_3-GND") (pintype "power_in"))
      (node (ref "LED2") (pin "3-GND") (pinfunction "GND_3-GND") (pintype "power_in"))
      (node (ref "LED20") (pin "3-GND") (pinfunction "GND_3-GND") (pintype "power_in"))
      (node (ref "LED3") (pin "3-GND") (pinfunction "GND_3-GND") (pintype "power_in"))
      (node (ref "LED4") (pin "3-GND") (pinfunction "GND_3-GND") (pintype "power_in"))
      (node (ref "LED5") (pin "3-GND") (pinfunction "GND_3-GND") (pintype "power_in"))
      (node (ref "LED6") (pin "3-GND") (pinfunction "GND_3-GND") (pintype "power_in"))
      (node (ref "LED7") (pin "3-GND") (pinfunction "GND_3-GND") (pintype "power_in"))
      (node (ref "LED8") (pin "3-GND") (pinfunction "GND_3-GND") (pintype "power_in"))
      (node (ref "LED9") (pin "3-GND") (pinfunction "GND_3-GND") (pintype "power_in"))
      (node (ref "MEMS_FRONT_EX") (pin "1") (pinfunction "LR_1") (pintype "input"))
      (node (ref "MEMS_FRONT_EX") (pin "2") (pinfunction "CONFIG_2") (pintype "input"))
      (node (ref "MEMS_FRONT_EX") (pin "4") (pinfunction "GND_4") (pintype "power_in"))
      (node (ref "MEMS_FRONT_STD") (pin "P$1") (pinfunction "GND_P$1") (pintype "power_in"))
      (node (ref "MEMS_REAR_EX") (pin "2") (pinfunction "CONFIG_2") (pintype "input"))
      (node (ref "MEMS_REAR_EX") (pin "4") (pinfunction "GND_4") (pintype "power_in"))
      (node (ref "MEMS_REAR_STD") (pin "2") (pinfunction "SELECT_2") (pintype "input"))
      (node (ref "MEMS_REAR_STD") (pin "P$1") (pinfunction "GND_P$1") (pintype "power_in"))
      (node (ref "P2") (pin "1") (pinfunction "1_1") (pintype "passive"))
      (node (ref "POT1") (pin "3") (pinfunction "3_3") (pintype "passive"))
      (node (ref "POT2") (pin "3") (pinfunction "3_3") (pintype "passive"))
      (node (ref "PWR") (pin "P$1") (pinfunction "P$1_P$1") (pintype "bidirectional"))
      (node (ref "R13") (pin "1") (pinfunction "1_1") (pintype "passive"))
      (node (ref "S3") (pin "1") (pinfunction "1_1") (pintype "passive"))
      (node (ref "SW1") (pin "1") (pinfunction "1_1") (pintype "passive"))
      (node (ref "SW1") (pin "2") (pinfunction "2_2") (pintype "passive"))
      (node (ref "SW1") (pin "3") (pinfunction "3_3") (pintype "passive"))
      (node (ref "SW1") (pin "4") (pinfunction "4_4") (pintype "passive"))
      (node (ref "SW1") (pin "5") (pinfunction "5_5") (pintype "passive"))
      (node (ref "SW1") (pin "6") (pinfunction "6_6") (pintype "passive"))
      (node (ref "U$3") (pin "GND") (pinfunction "GND_GND") (pintype "power_in"))
      (node (ref "U$4") (pin "P$3") (pinfunction "P$3_P$3") (pintype "bidirectional"))
      (node (ref "U$5") (pin "P$7") (pinfunction "P$7_P$7") (pintype "bidirectional"))
      (node (ref "U$5") (pin "P$8") (pinfunction "P$8_P$8") (pintype "bidirectional"))
      (node (ref "U$5") (pin "P$9") (pinfunction "P$9_P$9") (pintype "bidirectional"))
      (node (ref "U$6") (pin "P$3") (pinfunction "P$3_P$3") (pintype "bidirectional"))
      (node (ref "U$7") (pin "5V-GND") (pinfunction "GND_5V-GND") (pintype "bidirectional"))
      (node (ref "U$8") (pin "GND1") (pinfunction "GND_GND1") (pintype "bidirectional"))
      (node (ref "U$8") (pin "GND2") (pinfunction "GND_GND2") (pintype "bidirectional"))
      (node (ref "U1") (pin "10") (pinfunction "RESV9_1215_10") (pintype "passive"))
      (node (ref "U1") (pin "11") (pinfunction "RESV9_1215_11") (pintype "passive"))
      (node (ref "U1") (pin "12") (pinfunction "RESV9_1215_12") (pintype "passive"))
      (node (ref "U1") (pin "13") (pinfunction "GND_13") (pintype "power_in"))
      (node (ref "U1") (pin "15") (pinfunction "RESV9_1215_15") (pintype "passive"))
      (node (ref "U1") (pin "4") (pinfunction "SA0/SDO_4") (pintype "output"))
      (node (ref "U1") (pin "8") (pinfunction "FSYNC_8") (pintype "input"))
      (node (ref "U1") (pin "9") (pinfunction "RESV9_1215_9") (pintype "passive"))
      (node (ref "U2") (pin "4") (pinfunction "VSS_4") (pintype "bidirectional"))
      (node (ref "U2") (pin "5") (pinfunction "VSS_5") (pintype "bidirectional"))
      (node (ref "U3") (pin "4") (pinfunction "GND_4") (pintype "power_in"))
      (node (ref "VMEL_FRONT") (pin "1") (pinfunction "GND_1") (pintype "power_in"))
      (node (ref "VMEL_FRONT") (pin "4") (pinfunction "ADDR_4") (pintype "bidirectional"))
      (node (ref "VMEL_REAR") (pin "1") (pinfunction "GND_1") (pintype "power_in"))
    )
    (net (code "18") (name "IMU_INT") (class "Default")
      (node (ref "U$3") (pin "20/A6") (pinfunction "20/A6/PWM_20/A6") (pintype "bidirectional"))
      (node (ref "U1") (pin "6") (pinfunction "INT_6") (pintype "output"))
    )
    (net (code "19") (name "LRCLK") (class "Default")
      (node (ref "MEMS_FRONT_EX") (pin "5") (pinfunction "WS_5") (pintype "input"))
      (node (ref "MEMS_FRONT_STD") (pin "1") (pinfunction "WS_1") (pintype "input"))
      (node (ref "MEMS_REAR_EX") (pin "5") (pinfunction "WS_5") (pintype "input"))
      (node (ref "MEMS_REAR_STD") (pin "1") (pinfunction "WS_1") (pintype "input"))
      (node (ref "R7") (pin "1") (pinfunction "1_1") (pintype "passive"))
    )
    (net (code "20") (name "MCLK") (class "Default")
      (node (ref "U$3") (pin "11") (pinfunction "11/MOSI_11") (pintype "bidirectional"))
    )
    (net (code "21") (name "MISO") (class "Default")
      (node (ref "J7") (pin "7") (pinfunction "DAT0_7") (pintype "passive"))
      (node (ref "U$3") (pin "12") (pinfunction "12/MISO_12") (pintype "bidirectional"))
    )
    (net (code "22") (name "MOSI") (class "Default")
      (node (ref "J7") (pin "3") (pinfunction "CMD_3") (pintype "passive"))
      (node (ref "U$3") (pin "7") (pinfunction "7/RX3_7") (pintype "bidirectional"))
    )
    (net (code "23") (name "NEO_PIX1") (class "Default")
      (node (ref "LED1") (pin "4-DIN") (pinfunction "DI_4-DIN") (pintype "input"))
      (node (ref "U$3") (pin "5") (pinfunction "5/PWM_5") (pintype "bidirectional"))
    )
    (net (code "24") (name "NEO_PIX1_OUT") (class "Default")
      (node (ref "LED16") (pin "2-DOUT") (pinfunction "DO_2-DOUT") (pintype "output"))
      (node (ref "LED17") (pin "4-DIN") (pinfunction "DI_4-DIN") (pintype "input"))
    )
    (net (code "25") (name "Net-(AUDIO_IN-Pad2)") (class "Default")
      (node (ref "AUDIO_IN") (pin "2") (pinfunction "2_2") (pintype "passive"))
      (node (ref "U$7") (pin "IN_L") (pinfunction "IN_L_IN_L") (pintype "bidirectional"))
    )
    (net (code "26") (name "Net-(AUDIO_IN-Pad3)") (class "Default")
      (node (ref "AUDIO_IN") (pin "3") (pinfunction "3_3") (pintype "passive"))
      (node (ref "U$7") (pin "IN_R") (pinfunction "IN_R_IN_R") (pintype "bidirectional"))
    )
    (net (code "27") (name "Net-(LED1-DO)") (class "Default")
      (node (ref "LED1") (pin "2-DOUT") (pinfunction "DO_2-DOUT") (pintype "output"))
      (node (ref "LED2") (pin "4-DIN") (pinfunction "DI_4-DIN") (pintype "input"))
    )
    (net (code "28") (name "Net-(LED2-DO)") (class "Default")
      (node (ref "LED2") (pin "2-DOUT") (pinfunction "DO_2-DOUT") (pintype "output"))
      (node (ref "LED3") (pin "4-DIN") (pinfunction "DI_4-DIN") (pintype "input"))
    )
    (net (code "29") (name "Net-(LED3-DO)") (class "Default")
      (node (ref "LED3") (pin "2-DOUT") (pinfunction "DO_2-DOUT") (pintype "output"))
      (node (ref "LED4") (pin "4-DIN") (pinfunction "DI_4-DIN") (pintype "input"))
    )
    (net (code "30") (name "Net-(LED4-DO)") (class "Default")
      (node (ref "LED4") (pin "2-DOUT") (pinfunction "DO_2-DOUT") (pintype "output"))
      (node (ref "LED5") (pin "4-DIN") (pinfunction "DI_4-DIN") (pintype "input"))
    )
    (net (code "31") (name "Net-(LED5-DO)") (class "Default")
      (node (ref "LED5") (pin "2-DOUT") (pinfunction "DO_2-DOUT") (pintype "output"))
      (node (ref "LED6") (pin "4-DIN") (pinfunction "DI_4-DIN") (pintype "input"))
    )
    (net (code "32") (name "Net-(LED6-DO)") (class "Default")
      (node (ref "LED6") (pin "2-DOUT") (pinfunction "DO_2-DOUT") (pintype "output"))
      (node (ref "LED7") (pin "4-DIN") (pinfunction "DI_4-DIN") (pintype "input"))
    )
    (net (code "33") (name "Net-(LED7-DO)") (class "Default")
      (node (ref "LED7") (pin "2-DOUT") (pinfunction "DO_2-DOUT") (pintype "output"))
      (node (ref "LED8") (pin "4-DIN") (pinfunction "DI_4-DIN") (pintype "input"))
    )
    (net (code "34") (name "Net-(LED8-DO)") (class "Default")
      (node (ref "LED8") (pin "2-DOUT") (pinfunction "DO_2-DOUT") (pintype "output"))
      (node (ref "LED9") (pin "4-DIN") (pinfunction "DI_4-DIN") (pintype "input"))
    )
    (net (code "35") (name "Net-(LED10-DI)") (class "Default")
      (node (ref "LED10") (pin "4-DIN") (pinfunction "DI_4-DIN") (pintype "input"))
      (node (ref "LED9") (pin "2-DOUT") (pinfunction "DO_2-DOUT") (pintype "output"))
    )
    (net (code "36") (name "Net-(LED10-DO)") (class "Default")
      (node (ref "LED10") (pin "2-DOUT") (pinfunction "DO_2-DOUT") (pintype "output"))
      (node (ref "LED11") (pin "4-DIN") (pinfunction "DI_4-DIN") (pintype "input"))
    )
    (net (code "37") (name "Net-(LED11-DO)") (class "Default")
      (node (ref "LED11") (pin "2-DOUT") (pinfunction "DO_2-DOUT") (pintype "output"))
      (node (ref "LED12") (pin "4-DIN") (pinfunction "DI_4-DIN") (pintype "input"))
    )
    (net (code "38") (name "Net-(LED12-DO)") (class "Default")
      (node (ref "LED12") (pin "2-DOUT") (pinfunction "DO_2-DOUT") (pintype "output"))
      (node (ref "LED13") (pin "4-DIN") (pinfunction "DI_4-DIN") (pintype "input"))
    )
    (net (code "39") (name "Net-(LED13-DO)") (class "Default")
      (node (ref "LED13") (pin "2-DOUT") (pinfunction "DO_2-DOUT") (pintype "output"))
      (node (ref "LED14") (pin "4-DIN") (pinfunction "DI_4-DIN") (pintype "input"))
    )
    (net (code "40") (name "Net-(LED14-DO)") (class "Default")
      (node (ref "LED14") (pin "2-DOUT") (pinfunction "DO_2-DOUT") (pintype "output"))
      (node (ref "LED15") (pin "4-DIN") (pinfunction "DI_4-DIN") (pintype "input"))
    )
    (net (code "41") (name "Net-(LED15-DO)") (class "Default")
      (node (ref "LED15") (pin "2-DOUT") (pinfunction "DO_2-DOUT") (pintype "output"))
      (node (ref "LED16") (pin "4-DIN") (pinfunction "DI_4-DIN") (pintype "input"))
    )
    (net (code "42") (name "Net-(LED17-DO)") (class "Default")
      (node (ref "LED17") (pin "2-DOUT") (pinfunction "DO_2-DOUT") (pintype "output"))
      (node (ref "LED18") (pin "4-DIN") (pinfunction "DI_4-DIN") (pintype "input"))
    )
    (net (code "43") (name "Net-(LED18-DO)") (class "Default")
      (node (ref "LED18") (pin "2-DOUT") (pinfunction "DO_2-DOUT") (pintype "output"))
      (node (ref "LED19") (pin "4-DIN") (pinfunction "DI_4-DIN") (pintype "input"))
    )
    (net (code "44") (name "Net-(LED19-DO)") (class "Default")
      (node (ref "LED19") (pin "2-DOUT") (pinfunction "DO_2-DOUT") (pintype "output"))
      (node (ref "LED20") (pin "4-DIN") (pinfunction "DI_4-DIN") (pintype "input"))
    )
    (net (code "45") (name "Net-(MEMS_FRONT_EX-SD)") (class "Default")
      (node (ref "MEMS_FRONT_EX") (pin "7") (pinfunction "SD_7") (pintype "output"))
      (node (ref "MEMS_FRONT_STD") (pin "6") (pinfunction "DATA_OUT_6") (pintype "output"))
      (node (ref "R14") (pin "1") (pinfunction "1_1") (pintype "passive"))
    )
    (net (code "46") (name "Net-(U$5-PadP$10)") (class "Default")
      (node (ref "U$5") (pin "P$10") (pinfunction "P$10_P$10") (pintype "bidirectional"))
      (node (ref "U$5") (pin "P$11") (pinfunction "P$11_P$11") (pintype "bidirectional"))
      (node (ref "U$5") (pin "P$12") (pinfunction "P$12_P$12") (pintype "bidirectional"))
      (node (ref "U$5") (pin "P$4") (pinfunction "P$4_P$4") (pintype "bidirectional"))
      (node (ref "U$5") (pin "P$5") (pinfunction "P$5_P$5") (pintype "bidirectional"))
      (node (ref "U$5") (pin "P$6") (pinfunction "P$6_P$6") (pintype "bidirectional"))
    )
    (net (code "47") (name "Net-(U$7-IN_GND)") (class "Default")
      (node (ref "AUDIO_IN") (pin "1") (pinfunction "1_1") (pintype "passive"))
      (node (ref "U$7") (pin "IN_G") (pinfunction "IN_GND_IN_G") (pintype "bidirectional"))
    )
    (net (code "48") (name "Net-(U$7-OUT_L+)") (class "Default")
      (node (ref "FOUT") (pin "1") (pinfunction "1_1") (pintype "passive"))
      (node (ref "FRONT_OUT") (pin "1") (pinfunction "1_1") (pintype "passive"))
      (node (ref "F_OUT") (pin "1") (pinfunction "1_1") (pintype "passive"))
      (node (ref "U$7") (pin "LOUT_H") (pinfunction "OUT_L+_LOUT_H") (pintype "bidirectional"))
    )
    (net (code "49") (name "Net-(U$7-OUT_L-)") (class "Default")
      (node (ref "FOUT") (pin "2") (pinfunction "2_2") (pintype "passive"))
      (node (ref "FRONT_OUT") (pin "2") (pinfunction "2_2") (pintype "passive"))
      (node (ref "F_OUT") (pin "2") (pinfunction "2_2") (pintype "passive"))
      (node (ref "U$7") (pin "LOUT_G") (pinfunction "OUT_L-_LOUT_G") (pintype "bidirectional"))
    )
    (net (code "50") (name "Net-(U$7-OUT_R+)") (class "Default")
      (node (ref "REAR_OUT") (pin "1") (pinfunction "1_1") (pintype "passive"))
      (node (ref "ROUT") (pin "1") (pinfunction "1_1") (pintype "passive"))
      (node (ref "R_OUT") (pin "1") (pinfunction "1_1") (pintype "passive"))
      (node (ref "U$7") (pin "ROUT_H") (pinfunction "OUT_R+_ROUT_H") (pintype "bidirectional"))
    )
    (net (code "51") (name "Net-(U$7-OUT_R-)") (class "Default")
      (node (ref "REAR_OUT") (pin "2") (pinfunction "2_2") (pintype "passive"))
      (node (ref "ROUT") (pin "2") (pinfunction "2_2") (pintype "passive"))
      (node (ref "R_OUT") (pin "2") (pinfunction "2_2") (pintype "passive"))
      (node (ref "U$7") (pin "ROUT_G") (pinfunction "OUT_R-_ROUT_G") (pintype "bidirectional"))
    )
    (net (code "52") (name "Net-(U3-VIN)") (class "Default")
      (node (ref "R10") (pin "2") (pinfunction "2_2") (pintype "passive"))
      (node (ref "U3") (pin "1") (pinfunction "VIN_1") (pintype "input"))
    )
    (net (code "53") (name "Net-(VMEL_FRONT-VDD)") (class "Default")
      (node (ref "C10") (pin "1") (pinfunction "1_1") (pintype "passive"))
      (node (ref "C8") (pin "1") (pinfunction "1_1") (pintype "passive"))
      (node (ref "R1") (pin "1") (pinfunction "1_1") (pintype "passive"))
      (node (ref "VMEL_FRONT") (pin "6") (pinfunction "VDD_6") (pintype "power_in"))
    )
    (net (code "54") (name "Net-(VMEL_REAR-ADDR)") (class "Default")
      (node (ref "C42") (pin "1") (pinfunction "1_1") (pintype "passive"))
      (node (ref "C43") (pin "1") (pinfunction "1_1") (pintype "passive"))
      (node (ref "R2") (pin "1") (pinfunction "1_1") (pintype "passive"))
      (node (ref "VMEL_REAR") (pin "4") (pinfunction "ADDR_4") (pintype "bidirectional"))
      (node (ref "VMEL_REAR") (pin "6") (pinfunction "VDD_6") (pintype "power_in"))
    )
    (net (code "55") (name "ONT") (class "Default")
      (node (ref "C37") (pin "1") (pinfunction "1_1") (pintype "passive"))
      (node (ref "U3") (pin "3") (pinfunction "ONT_3") (pintype "input"))
    )
    (net (code "56") (name "PDT") (class "Default")
      (node (ref "C2") (pin "1") (pinfunction "1_1") (pintype "passive"))
      (node (ref "U3") (pin "7") (pinfunction "PDT_7") (pintype "input"))
    )
    (net (code "57") (name "POT1") (class "Default")
      (node (ref "POT1") (pin "2") (pinfunction "2_2") (pintype "passive"))
      (node (ref "U$3") (pin "17/A3") (pinfunction "17/A3/T_17/A3") (pintype "bidirectional"))
      (node (ref "U$4") (pin "P$1") (pinfunction "P$1_P$1") (pintype "bidirectional"))
    )
    (net (code "58") (name "POT2") (class "Default")
      (node (ref "POT2") (pin "2") (pinfunction "2_2") (pintype "passive"))
      (node (ref "U$3") (pin "21/A7") (pinfunction "21/A7/PWM_21/A7") (pintype "bidirectional"))
      (node (ref "U$6") (pin "P$1") (pinfunction "P$1_P$1") (pintype "bidirectional"))
    )
    (net (code "59") (name "PWR_INT") (class "Default")
      (node (ref "R8") (pin "1") (pinfunction "1_1") (pintype "passive"))
      (node (ref "U$3") (pin "15/A1") (pinfunction "15/A1/T_15/A1") (pintype "bidirectional"))
      (node (ref "U3") (pin "5") (pinfunction "*INT_5") (pintype "output"))
    )
    (net (code "60") (name "PWR_KILL") (class "Default")
      (node (ref "U$3") (pin "8") (pinfunction "8/TX3_8") (pintype "bidirectional"))
      (node (ref "U3") (pin "8") (pinfunction "*KILL_8") (pintype "input"))
    )
    (net (code "61") (name "REAR_PRE_R") (class "Default")
      (node (ref "MEMS_REAR_EX") (pin "7") (pinfunction "SD_7") (pintype "output"))
      (node (ref "MEMS_REAR_STD") (pin "6") (pinfunction "DATA_OUT_6") (pintype "output"))
      (node (ref "R16") (pin "1") (pinfunction "1_1") (pintype "passive"))
    )
    (net (code "62") (name "SCL") (class "Default")
      (node (ref "R4") (pin "1") (pinfunction "1_1") (pintype "passive"))
      (node (ref "U$3") (pin "19/A5") (pinfunction "19/A5/T/SCL0_19/A5") (pintype "bidirectional"))
      (node (ref "U1") (pin "2") (pinfunction "SCL/SPC_2") (pintype "bidirectional"))
      (node (ref "U2") (pin "2") (pinfunction "SCL_2") (pintype "bidirectional"))
      (node (ref "VMEL_FRONT") (pin "5") (pinfunction "SCL_5") (pintype "input"))
      (node (ref "VMEL_REAR") (pin "5") (pinfunction "SCL_5") (pintype "input"))
    )
    (net (code "63") (name "SDA") (class "Default")
      (node (ref "R3") (pin "1") (pinfunction "1_1") (pintype "passive"))
      (node (ref "U$3") (pin "18/A4") (pinfunction "18/A4/T/SDA0_18/A4") (pintype "bidirectional"))
      (node (ref "U1") (pin "3") (pinfunction "SDA/SDI_3") (pintype "input"))
      (node (ref "U2") (pin "3") (pinfunction "SDA_3") (pintype "bidirectional"))
      (node (ref "VMEL_FRONT") (pin "2") (pinfunction "SDA_2") (pintype "bidirectional"))
      (node (ref "VMEL_REAR") (pin "2") (pinfunction "SDA_2") (pintype "bidirectional"))
    )
    (net (code "64") (name "SD_CS") (class "Default")
      (node (ref "J7") (pin "2") (pinfunction "CD/DAT3_2") (pintype "passive"))
      (node (ref "R11") (pin "1") (pinfunction "1_1") (pintype "passive"))
      (node (ref "U$3") (pin "10") (pinfunction "10/TX2/PWM_10") (pintype "bidirectional"))
    )
    (net (code "65") (name "SPI_CLK") (class "Default")
      (node (ref "J7") (pin "5") (pinfunction "CLK_5") (pintype "passive"))
      (node (ref "U$3") (pin "14/A0") (pinfunction "14/A1_14/A0") (pintype "bidirectional"))
    )
    (net (code "66") (name "VEML_INT_1") (class "Default")
      (node (ref "VMEL_FRONT") (pin "3") (pinfunction "INT_3") (pintype "output"))
    )
    (net (code "67") (name "VEML_INT_2") (class "Default")
      (node (ref "VMEL_REAR") (pin "3") (pinfunction "INT_3") (pintype "output"))
    )
    (net (code "68") (name "_BCLK") (class "Default")
      (node (ref "R5") (pin "2") (pinfunction "2_2") (pintype "passive"))
      (node (ref "U$3") (pin "9") (pinfunction "9/RX2/PWM_9") (pintype "bidirectional"))
    )
    (net (code "69") (name "_LRCLK") (class "Default")
      (node (ref "R7") (pin "2") (pinfunction "2_2") (pintype "passive"))
      (node (ref "U$3") (pin "23/A9") (pinfunction "23/A9/T/PWM_23/A9") (pintype "bidirectional"))
    )
    (net (code "70") (name "unconnected-(J7-CD_SW-Pad9)") (class "Default")
      (node (ref "J7") (pin "9") (pinfunction "CD_SW_9") (pintype "passive"))
    )
    (net (code "71") (name "unconnected-(J7-DAT1-Pad8)") (class "Default")
      (node (ref "J7") (pin "8") (pinfunction "DAT1_8") (pintype "passive"))
    )
    (net (code "72") (name "unconnected-(J7-DAT2-Pad1)") (class "Default")
      (node (ref "J7") (pin "1") (pinfunction "DAT2_1") (pintype "passive"))
    )
    (net (code "73") (name "unconnected-(LED20-DO-Pad2-DOUT)") (class "Default")
      (node (ref "LED20") (pin "2-DOUT") (pinfunction "DO_2-DOUT") (pintype "output"))
    )
    (net (code "74") (name "unconnected-(PWR-PadP$2)") (class "Default")
      (node (ref "PWR") (pin "P$2") (pinfunction "P$2_P$2") (pintype "bidirectional"))
    )
    (net (code "75") (name "unconnected-(U1-REGOUT-Pad14)") (class "Default")
      (node (ref "U1") (pin "14") (pinfunction "REGOUT_14") (pintype "passive"))
    )
    (net (code "76") (name "unconnected-(U1-RESV7-Pad7)") (class "Default")
      (node (ref "U1") (pin "7") (pinfunction "RESV7_7") (pintype "passive"))
    )
  )
)
